# Jig-Lower-Layer.net
KiCad netlist of a schematic drawn in EAGLE
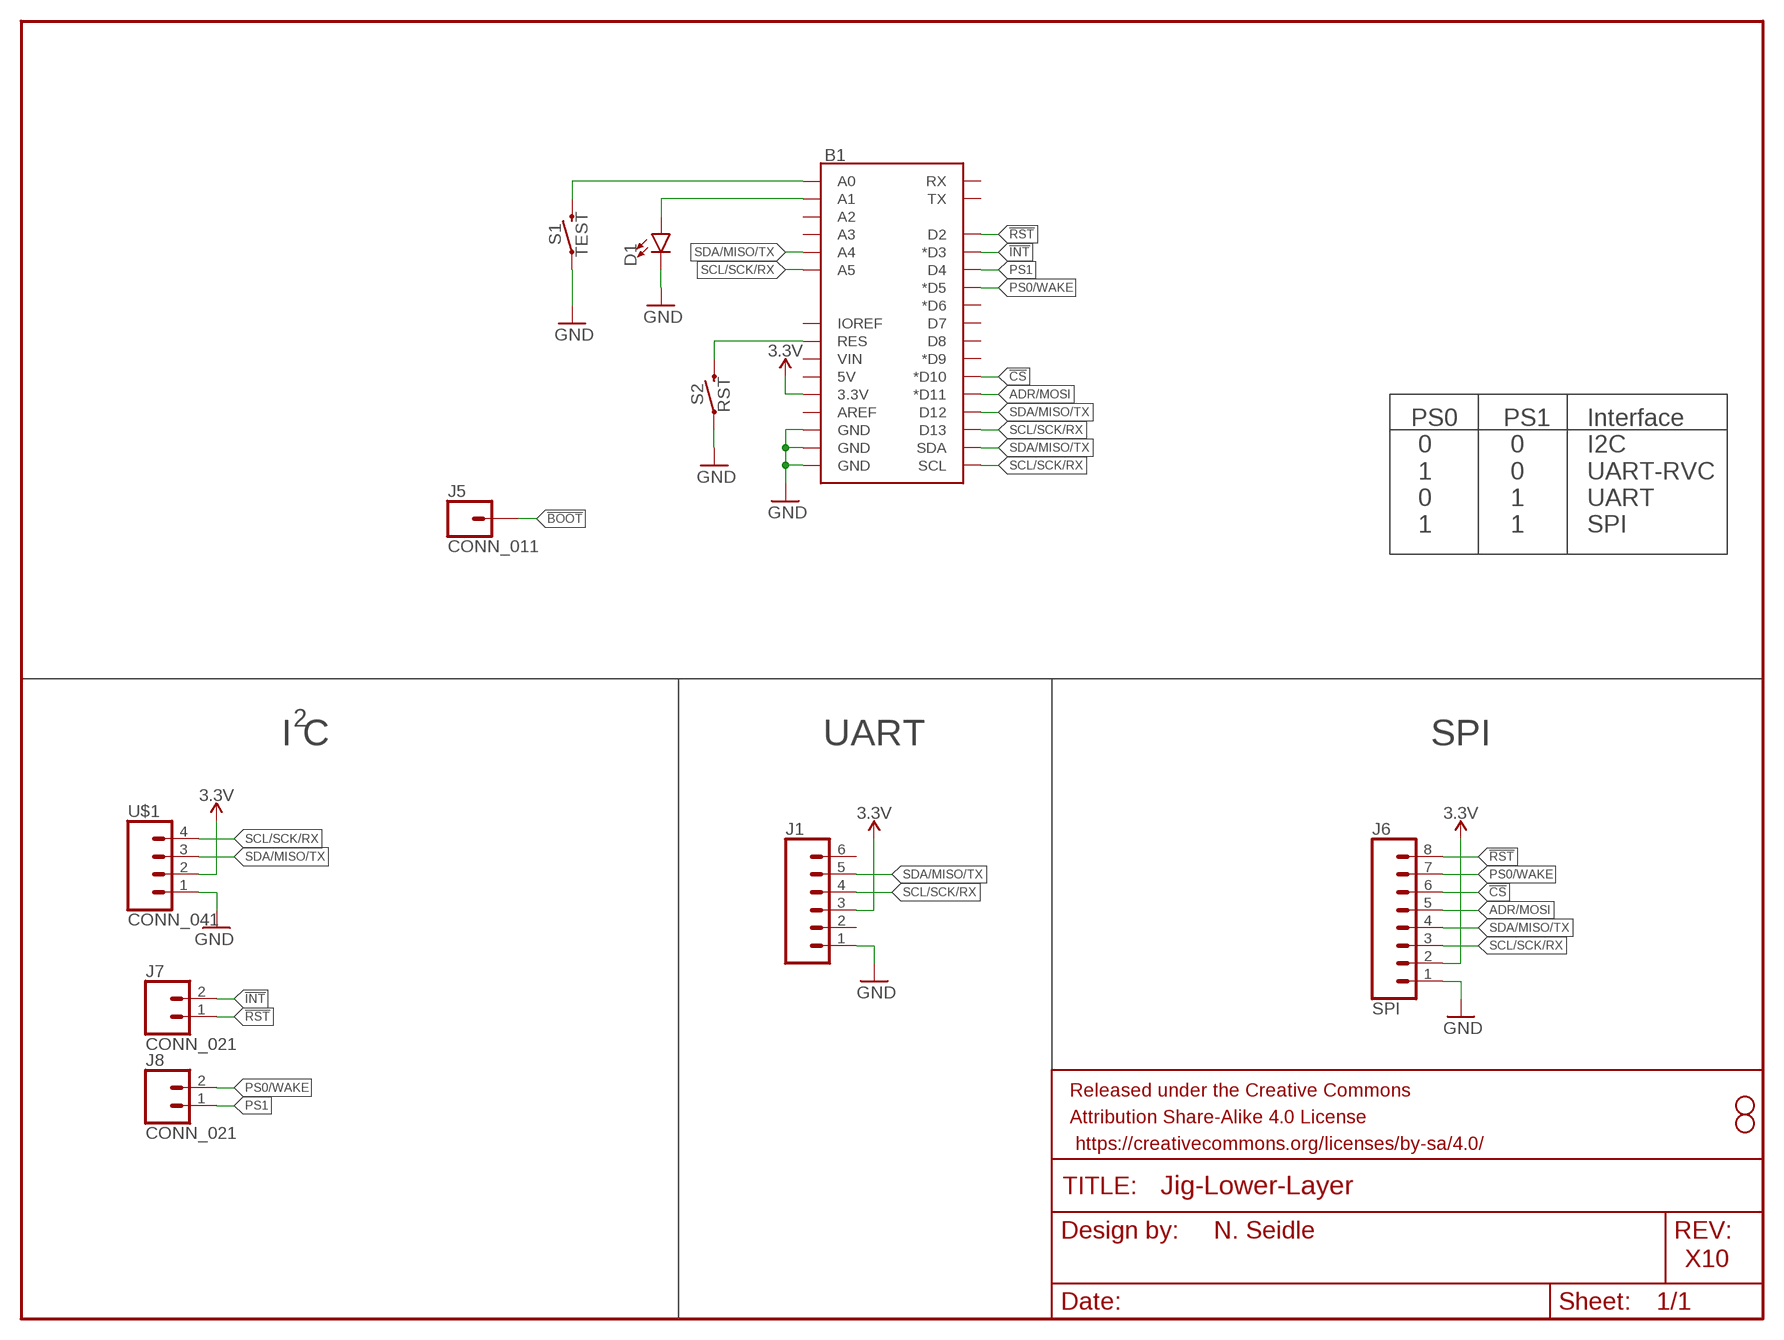
[diagram p0: schematic, sheet 1]

(export (version "E")
  (design (tool "Eeschema 10.0.6"))
  (components
    (comp (ref "B1")
      (value "ARDUINO_UNO_R3_SHIELDBASIC")
      (footprint "eagle-import:UNO_R3_SHIELD")
      (libsource (lib "eagle-import") (part "ARDUINO_UNO_R3_SHIELDBASIC"))
    )
    (comp (ref "D1")
      (value "LED5MM")
      (footprint "eagle-import:LED_5MM")
      (libsource (lib "eagle-import") (part "LED5MM"))
    )
    (comp (ref "FRAME1")
      (value "FRAME-LETTER")
      (footprint "eagle-import:CREATIVE_COMMONS")
      (libsource (lib "eagle-import") (part "FRAME-LETTER"))
    )
    (comp (ref "J1")
      (value "CONN_061")
      (footprint "eagle-import:1X06")
      (libsource (lib "eagle-import") (part "CONN_061"))
    )
    (comp (ref "J5")
      (value "CONN_011")
      (footprint "eagle-import:1X01")
      (libsource (lib "eagle-import") (part "CONN_011"))
    )
    (comp (ref "J6")
      (value "SPI")
      (footprint "eagle-import:1X08")
      (libsource (lib "eagle-import") (part "CONN_081"))
    )
    (comp (ref "J7")
      (value "CONN_021")
      (footprint "eagle-import:1X02")
      (libsource (lib "eagle-import") (part "CONN_021"))
    )
    (comp (ref "J8")
      (value "CONN_021")
      (footprint "eagle-import:1X02")
      (libsource (lib "eagle-import") (part "CONN_021"))
    )
    (comp (ref "JP3")
      (value "STAND-OFF")
      (footprint "eagle-import:STAND-OFF")
      (libsource (lib "eagle-import") (part "STAND-OFF"))
    )
    (comp (ref "JP4")
      (value "STAND-OFF")
      (footprint "eagle-import:STAND-OFF")
      (libsource (lib "eagle-import") (part "STAND-OFF"))
    )
    (comp (ref "S1")
      (value "TEST")
      (footprint "eagle-import:TACTILE_SWITCH_PTH_12MM")
      (libsource (lib "eagle-import") (part "MOMENTARY-SWITCH-SPST-PTH-12MM"))
    )
    (comp (ref "S2")
      (value "RST")
      (footprint "eagle-import:TACTILE_SWITCH_PTH_12MM")
      (libsource (lib "eagle-import") (part "MOMENTARY-SWITCH-SPST-PTH-12MM"))
    )
    (comp (ref "U$1")
      (value "CONN_041")
      (footprint "eagle-import:1X04")
      (libsource (lib "eagle-import") (part "CONN_041"))
    )
  )
  (nets
    (net (code "1") (name "/~{BOOT}") (class "Default")
      (node (ref "J5") (pin "1") (pinfunction "1_1") (pintype "passive"))
    )
    (net (code "2") (name "/~{CS}") (class "Default")
      (node (ref "B1") (pin "D10") (pinfunction "*D10_D10") (pintype "bidirectional"))
      (node (ref "J6") (pin "6") (pinfunction "6_6") (pintype "passive"))
    )
    (net (code "3") (name "/~{INT}") (class "Default")
      (node (ref "B1") (pin "D3") (pinfunction "*D3_D3") (pintype "bidirectional"))
      (node (ref "J7") (pin "2") (pinfunction "2_2") (pintype "passive"))
    )
    (net (code "4") (name "/~{RST}") (class "Default")
      (node (ref "B1") (pin "D2") (pinfunction "D2_D2") (pintype "bidirectional"))
      (node (ref "J6") (pin "8") (pinfunction "8_8") (pintype "passive"))
      (node (ref "J7") (pin "1") (pinfunction "1_1") (pintype "passive"))
    )
    (net (code "5") (name "3.3V") (class "Default")
      (node (ref "B1") (pin "3.3V") (pinfunction "3.3V_3.3V") (pintype "bidirectional"))
      (node (ref "J1") (pin "3") (pinfunction "3_3") (pintype "passive"))
      (node (ref "J6") (pin "2") (pinfunction "2_2") (pintype "passive"))
      (node (ref "U$1") (pin "2") (pinfunction "2_2") (pintype "passive"))
    )
    (net (code "6") (name "ADR{slash}MOSI") (class "Default")
      (node (ref "B1") (pin "D11") (pinfunction "*D11_D11") (pintype "bidirectional"))
      (node (ref "J6") (pin "5") (pinfunction "5_5") (pintype "passive"))
    )
    (net (code "7") (name "GND") (class "Default")
      (node (ref "B1") (pin "GND@0") (pinfunction "GND_GND@0") (pintype "bidirectional"))
      (node (ref "B1") (pin "GND@1") (pinfunction "GND_GND@1") (pintype "bidirectional"))
      (node (ref "B1") (pin "GND@2") (pinfunction "GND_GND@2") (pintype "bidirectional"))
      (node (ref "D1") (pin "K") (pinfunction "C_K") (pintype "passive"))
      (node (ref "J1") (pin "1") (pinfunction "1_1") (pintype "passive"))
      (node (ref "J6") (pin "1") (pinfunction "1_1") (pintype "passive"))
      (node (ref "S1") (pin "1") (pinfunction "1_1") (pintype "passive"))
      (node (ref "S2") (pin "1") (pinfunction "1_1") (pintype "passive"))
      (node (ref "U$1") (pin "1") (pinfunction "1_1") (pintype "passive"))
    )
    (net (code "8") (name "Net-(B1-PadA1)") (class "Default")
      (node (ref "B1") (pin "A1") (pinfunction "A1_A1") (pintype "bidirectional"))
      (node (ref "D1") (pin "A") (pinfunction "A_A") (pintype "passive"))
    )
    (net (code "9") (name "Net-(S1-2)") (class "Default")
      (node (ref "B1") (pin "A0") (pinfunction "A0_A0") (pintype "bidirectional"))
      (node (ref "S1") (pin "3") (pinfunction "2_3") (pintype "passive"))
    )
    (net (code "10") (name "Net-(S2-2)") (class "Default")
      (node (ref "B1") (pin "RES") (pinfunction "RES_RES") (pintype "bidirectional"))
      (node (ref "S2") (pin "3") (pinfunction "2_3") (pintype "passive"))
    )
    (net (code "11") (name "PS0{slash}WAKE") (class "Default")
      (node (ref "B1") (pin "D5") (pinfunction "*D5_D5") (pintype "bidirectional"))
      (node (ref "J6") (pin "7") (pinfunction "7_7") (pintype "passive"))
      (node (ref "J8") (pin "2") (pinfunction "2_2") (pintype "passive"))
    )
    (net (code "12") (name "PS1") (class "Default")
      (node (ref "B1") (pin "D4") (pinfunction "D4_D4") (pintype "bidirectional"))
      (node (ref "J8") (pin "1") (pinfunction "1_1") (pintype "passive"))
    )
    (net (code "13") (name "SCL{slash}SCK{slash}RX") (class "Default")
      (node (ref "B1") (pin "A5") (pinfunction "A5_A5") (pintype "bidirectional"))
      (node (ref "B1") (pin "D13") (pinfunction "D13_D13") (pintype "bidirectional"))
      (node (ref "B1") (pin "SCL") (pinfunction "SCL_SCL") (pintype "bidirectional"))
      (node (ref "J1") (pin "4") (pinfunction "4_4") (pintype "passive"))
      (node (ref "J6") (pin "3") (pinfunction "3_3") (pintype "passive"))
      (node (ref "U$1") (pin "4") (pinfunction "4_4") (pintype "passive"))
    )
    (net (code "14") (name "SDA{slash}MISO{slash}TX") (class "Default")
      (node (ref "B1") (pin "A4") (pinfunction "A4_A4") (pintype "bidirectional"))
      (node (ref "B1") (pin "D12") (pinfunction "D12_D12") (pintype "bidirectional"))
      (node (ref "B1") (pin "SDA") (pinfunction "SDA_SDA") (pintype "bidirectional"))
      (node (ref "J1") (pin "5") (pinfunction "5_5") (pintype "passive"))
      (node (ref "J6") (pin "4") (pinfunction "4_4") (pintype "passive"))
      (node (ref "U$1") (pin "3") (pinfunction "3_3") (pintype "passive"))
    )
    (net (code "15") (name "unconnected-(B1-*D6-PadD6)") (class "Default")
      (node (ref "B1") (pin "D6") (pinfunction "*D6_D6") (pintype "bidirectional"))
    )
    (net (code "16") (name "unconnected-(B1-*D9-PadD9)") (class "Default")
      (node (ref "B1") (pin "D9") (pinfunction "*D9_D9") (pintype "bidirectional"))
    )
    (net (code "17") (name "unconnected-(B1-Pad5V)") (class "Default")
      (node (ref "B1") (pin "5V") (pinfunction "5V_5V") (pintype "bidirectional"))
    )
    (net (code "18") (name "unconnected-(B1-PadA2)") (class "Default")
      (node (ref "B1") (pin "A2") (pinfunction "A2_A2") (pintype "bidirectional"))
    )
    (net (code "19") (name "unconnected-(B1-PadA3)") (class "Default")
      (node (ref "B1") (pin "A3") (pinfunction "A3_A3") (pintype "bidirectional"))
    )
    (net (code "20") (name "unconnected-(B1-PadAREF)") (class "Default")
      (node (ref "B1") (pin "AREF") (pinfunction "AREF_AREF") (pintype "bidirectional"))
    )
    (net (code "21") (name "unconnected-(B1-PadD7)") (class "Default")
      (node (ref "B1") (pin "D7") (pinfunction "D7_D7") (pintype "bidirectional"))
    )
    (net (code "22") (name "unconnected-(B1-PadD8)") (class "Default")
      (node (ref "B1") (pin "D8") (pinfunction "D8_D8") (pintype "bidirectional"))
    )
    (net (code "23") (name "unconnected-(B1-PadIOREF)") (class "Default")
      (node (ref "B1") (pin "IOREF") (pinfunction "IOREF_IOREF") (pintype "bidirectional"))
    )
    (net (code "24") (name "unconnected-(B1-PadRX)") (class "Default")
      (node (ref "B1") (pin "RX") (pinfunction "RX_RX") (pintype "bidirectional"))
    )
    (net (code "25") (name "unconnected-(B1-PadTX)") (class "Default")
      (node (ref "B1") (pin "TX") (pinfunction "TX_TX") (pintype "bidirectional"))
    )
    (net (code "26") (name "unconnected-(B1-PadVIN)") (class "Default")
      (node (ref "B1") (pin "VIN") (pinfunction "VIN_VIN") (pintype "bidirectional"))
    )
    (net (code "27") (name "unconnected-(J1-Pad2)") (class "Default")
      (node (ref "J1") (pin "2") (pinfunction "2_2") (pintype "passive"))
    )
    (net (code "28") (name "unconnected-(J1-Pad6)") (class "Default")
      (node (ref "J1") (pin "6") (pinfunction "6_6") (pintype "passive"))
    )
  )
)
